# Filter_Load.net
KiCad netlist of a schematic drawn in Altium Designer
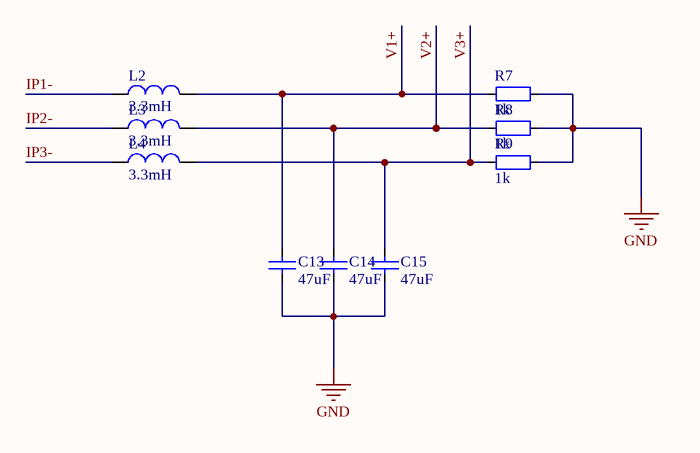
[diagram p0: Filter_Load.SchDoc]

(export (version "E")
  (design (tool "Eeschema 10.0.6"))
  (components
    (comp (ref "C13")
      (value "47uF")
      (footprint "CAP_0402")
      (description "Capacitor")
      (fields (field (name "PUBLISHER") "Altium Limited"))
      (libsource (lib "My Library_1") (part "CapSMD"))
    )
    (comp (ref "C14")
      (value "47uF")
      (footprint "CAP_0402")
      (description "Capacitor")
      (fields (field (name "PUBLISHER") "Altium Limited"))
      (libsource (lib "My Library_1") (part "CapSMD"))
    )
    (comp (ref "C15")
      (value "47uF")
      (footprint "CAP_0402")
      (description "Capacitor")
      (fields (field (name "PUBLISHER") "Altium Limited"))
      (libsource (lib "My Library_1") (part "CapSMD"))
    )
    (comp (ref "L2")
      (value "3.3mH")
      (footprint "Inductor")
      (description "Inductor")
      (libsource (lib "My Library_1") (part "Inductor"))
    )
    (comp (ref "L3")
      (value "3.3mH")
      (footprint "Inductor")
      (description "Inductor")
      (libsource (lib "My Library_1") (part "Inductor"))
    )
    (comp (ref "L4")
      (value "3.3mH")
      (footprint "Inductor")
      (description "Inductor")
      (libsource (lib "My Library_1") (part "Inductor"))
    )
    (comp (ref "R7")
      (value "1k")
      (footprint "RES-SMD-0101")
      (description "Resistor")
      (fields
        (field (name "MANUFACTURER") "Generic Components")
        (field (name "PUBLISHER") "Altium Hobart Technology Centre")
      )
      (libsource (lib "My Library_1") (part "Resistor - SMD"))
    )
    (comp (ref "R8")
      (value "1k")
      (footprint "RES-SMD-0101")
      (description "Resistor")
      (fields
        (field (name "MANUFACTURER") "Generic Components")
        (field (name "PUBLISHER") "Altium Hobart Technology Centre")
      )
      (libsource (lib "My Library_1") (part "Resistor - SMD"))
    )
    (comp (ref "R9")
      (value "1k")
      (footprint "RES-SMD-0101")
      (description "Resistor")
      (fields
        (field (name "MANUFACTURER") "Generic Components")
        (field (name "PUBLISHER") "Altium Hobart Technology Centre")
      )
      (libsource (lib "My Library_1") (part "Resistor - SMD"))
    )
  )
  (nets
    (net (code "1") (name "/IP1-") (class "Default")
      (node (ref "L2") (pin "1") (pinfunction "1_1") (pintype "passive"))
    )
    (net (code "2") (name "/IP2-") (class "Default")
      (node (ref "L3") (pin "1") (pinfunction "1_1") (pintype "passive"))
    )
    (net (code "3") (name "/IP3-") (class "Default")
      (node (ref "L4") (pin "1") (pinfunction "1_1") (pintype "passive"))
    )
    (net (code "4") (name "/V1+") (class "Default")
      (node (ref "C13") (pin "2") (pinfunction "2_2") (pintype "passive"))
      (node (ref "L2") (pin "2") (pinfunction "2_2") (pintype "passive"))
      (node (ref "R7") (pin "1") (pinfunction "1_1") (pintype "passive"))
    )
    (net (code "5") (name "/V2+") (class "Default")
      (node (ref "C14") (pin "2") (pinfunction "2_2") (pintype "passive"))
      (node (ref "L3") (pin "2") (pinfunction "2_2") (pintype "passive"))
      (node (ref "R8") (pin "1") (pinfunction "1_1") (pintype "passive"))
    )
    (net (code "6") (name "/V3+") (class "Default")
      (node (ref "C15") (pin "2") (pinfunction "2_2") (pintype "passive"))
      (node (ref "L4") (pin "2") (pinfunction "2_2") (pintype "passive"))
      (node (ref "R9") (pin "1") (pinfunction "1_1") (pintype "passive"))
    )
    (net (code "7") (name "GND") (class "Default")
      (node (ref "C13") (pin "1") (pinfunction "1_1") (pintype "passive"))
      (node (ref "C14") (pin "1") (pinfunction "1_1") (pintype "passive"))
      (node (ref "C15") (pin "1") (pinfunction "1_1") (pintype "passive"))
      (node (ref "R7") (pin "2") (pinfunction "2_2") (pintype "passive"))
      (node (ref "R8") (pin "2") (pinfunction "2_2") (pintype "passive"))
      (node (ref "R9") (pin "2") (pinfunction "2_2") (pintype "passive"))
    )
  )
)
